# WR.net
KiCad netlist of a schematic drawn in Altium Designer
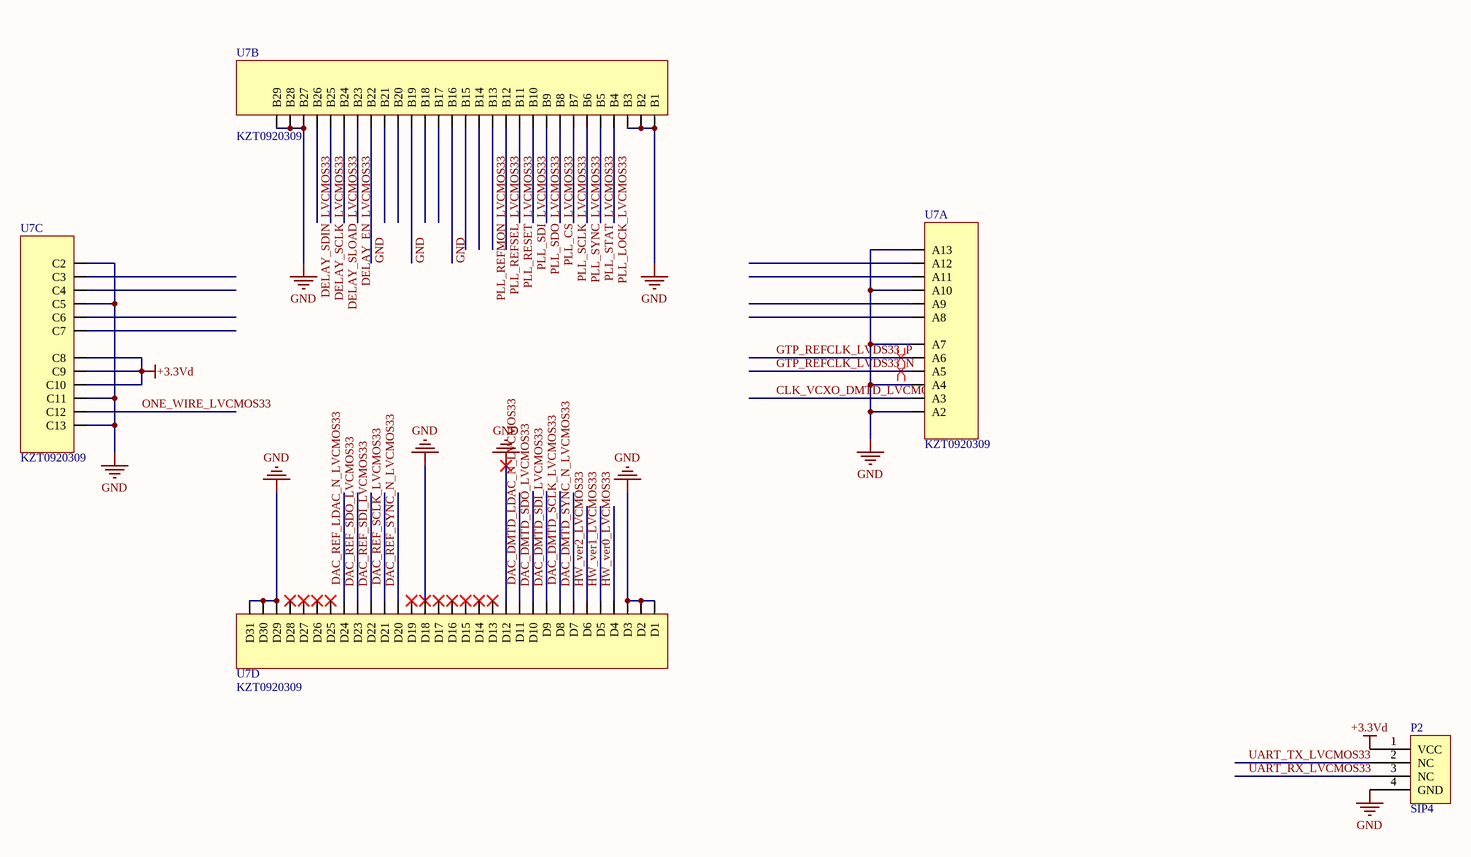
[diagram p0: WR.SchDoc]

(export (version "E")
  (design (tool "Eeschema 10.0.6"))
  (components
    (comp (ref "P2") (value "SIP4") (footprint "HDR1X4") (libsource (lib "LIB01DXP2006SchLib") (part "SIP4")))
    (comp (ref "U7")
      (value "KZT0920309")
      (footprint "KZT0920309")
      (description "NEM&MINI Socket")
      (libsource (lib "LIB01DXP2006SchLib") (part "KZT0920309"))
    )
  )
  (nets
    (net (code "1") (name "+3.3Vd") (class "Default")
      (node (ref "P2") (pin "1") (pinfunction "VCC_1") (pintype "passive"))
      (node (ref "U7") (pin "C10") (pinfunction "C10_C10") (pintype "passive"))
      (node (ref "U7") (pin "C8") (pinfunction "C8_C8") (pintype "passive"))
      (node (ref "U7") (pin "C9") (pinfunction "C9_C9") (pintype "passive"))
    )
    (net (code "2") (name "/CLK_VCXO_DMTD_LVCMOS33") (class "Default")
      (node (ref "U7") (pin "A3") (pinfunction "A3_A3") (pintype "passive"))
    )
    (net (code "3") (name "/DAC_DMTD_LDAC_N_LVCMOS33") (class "Default")
      (node (ref "U7") (pin "D11") (pinfunction "D11_D11") (pintype "power_in"))
    )
    (net (code "4") (name "/DAC_DMTD_SCLK_LVCMOS33") (class "Default")
      (node (ref "U7") (pin "D8") (pinfunction "D8_D8") (pintype "power_in"))
    )
    (net (code "5") (name "/DAC_DMTD_SDI_LVCMOS33") (class "Default")
      (node (ref "U7") (pin "D9") (pinfunction "D9_D9") (pintype "power_in"))
    )
    (net (code "6") (name "/DAC_DMTD_SDO_LVCMOS33") (class "Default")
      (node (ref "U7") (pin "D10") (pinfunction "D10_D10") (pintype "power_in"))
    )
    (net (code "7") (name "/DAC_DMTD_SYNC_N_LVCMOS33") (class "Default")
      (node (ref "U7") (pin "D7") (pinfunction "D7_D7") (pintype "power_in"))
    )
    (net (code "8") (name "/DAC_REF_LDAC_N_LVCMOS33") (class "Default")
      (node (ref "U7") (pin "D24") (pinfunction "D24_D24") (pintype "power_in"))
    )
    (net (code "9") (name "/DAC_REF_SCLK_LVCMOS33") (class "Default")
      (node (ref "U7") (pin "D21") (pinfunction "D21_D21") (pintype "power_in"))
    )
    (net (code "10") (name "/DAC_REF_SDI_LVCMOS33") (class "Default")
      (node (ref "U7") (pin "D22") (pinfunction "D22_D22") (pintype "power_in"))
    )
    (net (code "11") (name "/DAC_REF_SDO_LVCMOS33") (class "Default")
      (node (ref "U7") (pin "D23") (pinfunction "D23_D23") (pintype "power_in"))
    )
    (net (code "12") (name "/DAC_REF_SYNC_N_LVCMOS33") (class "Default")
      (node (ref "U7") (pin "D20") (pinfunction "D20_D20") (pintype "power_in"))
    )
    (net (code "13") (name "/DELAY_EN_LVCMOS33") (class "Default")
      (node (ref "U7") (pin "B23") (pinfunction "B23_B23") (pintype "power_in"))
    )
    (net (code "14") (name "/DELAY_SCLK_LVCMOS33") (class "Default")
      (node (ref "U7") (pin "B25") (pinfunction "B25_B25") (pintype "power_in"))
    )
    (net (code "15") (name "/DELAY_SDIN_LVCMOS33") (class "Default")
      (node (ref "U7") (pin "B26") (pinfunction "B26_B26") (pintype "power_in"))
    )
    (net (code "16") (name "/DELAY_SLOAD_LVCMOS33") (class "Default")
      (node (ref "U7") (pin "B24") (pinfunction "B24_B24") (pintype "power_in"))
    )
    (net (code "17") (name "/GTP_REFCLK_LVDS33_N") (class "Default")
      (node (ref "U7") (pin "A5") (pinfunction "A5_A5") (pintype "passive"))
    )
    (net (code "18") (name "/GTP_REFCLK_LVDS33_P") (class "Default")
      (node (ref "U7") (pin "A6") (pinfunction "A6_A6") (pintype "passive"))
    )
    (net (code "19") (name "/HW_ver0_LVCMOS33") (class "Default")
      (node (ref "U7") (pin "D4") (pinfunction "D4_D4") (pintype "power_in"))
    )
    (net (code "20") (name "/HW_ver1_LVCMOS33") (class "Default")
      (node (ref "U7") (pin "D5") (pinfunction "D5_D5") (pintype "power_in"))
    )
    (net (code "21") (name "/HW_ver2_LVCMOS33") (class "Default")
      (node (ref "U7") (pin "D6") (pinfunction "D6_D6") (pintype "power_in"))
    )
    (net (code "22") (name "/ONE_WIRE_LVCMOS33") (class "Default")
      (node (ref "U7") (pin "C12") (pinfunction "C12_C12") (pintype "passive"))
    )
    (net (code "23") (name "/PLL_CS_LVCMOS33") (class "Default")
      (node (ref "U7") (pin "B8") (pinfunction "B8_B8") (pintype "power_in"))
    )
    (net (code "24") (name "/PLL_LOCK_LVCMOS33") (class "Default")
      (node (ref "U7") (pin "B4") (pinfunction "B4_B4") (pintype "power_in"))
    )
    (net (code "25") (name "/PLL_REFMON_LVCMOS33") (class "Default")
      (node (ref "U7") (pin "B13") (pinfunction "B13_B13") (pintype "power_in"))
    )
    (net (code "26") (name "/PLL_REFSEL_LVCMOS33") (class "Default")
      (node (ref "U7") (pin "B12") (pinfunction "B12_B12") (pintype "power_in"))
    )
    (net (code "27") (name "/PLL_RESET_LVCMOS33") (class "Default")
      (node (ref "U7") (pin "B11") (pinfunction "B11_B11") (pintype "power_in"))
    )
    (net (code "28") (name "/PLL_SCLK_LVCMOS33") (class "Default")
      (node (ref "U7") (pin "B7") (pinfunction "B7_B7") (pintype "power_in"))
    )
    (net (code "29") (name "/PLL_SDI_LVCMOS33") (class "Default")
      (node (ref "U7") (pin "B10") (pinfunction "B10_B10") (pintype "power_in"))
    )
    (net (code "30") (name "/PLL_SDO_LVCMOS33") (class "Default")
      (node (ref "U7") (pin "B9") (pinfunction "B9_B9") (pintype "power_in"))
    )
    (net (code "31") (name "/PLL_STAT_LVCMOS33") (class "Default")
      (node (ref "U7") (pin "B5") (pinfunction "B5_B5") (pintype "power_in"))
    )
    (net (code "32") (name "/PLL_SYNC_LVCMOS33") (class "Default")
      (node (ref "U7") (pin "B6") (pinfunction "B6_B6") (pintype "power_in"))
    )
    (net (code "33") (name "/UART_RX_LVCMOS33") (class "Default")
      (node (ref "P2") (pin "3") (pinfunction "NC_3") (pintype "passive"))
    )
    (net (code "34") (name "/UART_TX_LVCMOS33") (class "Default")
      (node (ref "P2") (pin "2") (pinfunction "NC_2") (pintype "passive"))
    )
    (net (code "35") (name "GND") (class "Default")
      (node (ref "P2") (pin "4") (pinfunction "GND_4") (pintype "passive"))
      (node (ref "U7") (pin "A10") (pinfunction "A10_A10") (pintype "passive"))
      (node (ref "U7") (pin "A13") (pinfunction "A13_A13") (pintype "passive"))
      (node (ref "U7") (pin "A2") (pinfunction "A2_A2") (pintype "passive"))
      (node (ref "U7") (pin "A4") (pinfunction "A4_A4") (pintype "passive"))
      (node (ref "U7") (pin "A7") (pinfunction "A7_A7") (pintype "passive"))
      (node (ref "U7") (pin "B1") (pinfunction "B1_B1") (pintype "power_in"))
      (node (ref "U7") (pin "B16") (pinfunction "B16_B16") (pintype "power_in"))
      (node (ref "U7") (pin "B19") (pinfunction "B19_B19") (pintype "power_in"))
      (node (ref "U7") (pin "B2") (pinfunction "B2_B2") (pintype "power_in"))
      (node (ref "U7") (pin "B22") (pinfunction "B22_B22") (pintype "power_in"))
      (node (ref "U7") (pin "B27") (pinfunction "B27_B27") (pintype "power_in"))
      (node (ref "U7") (pin "B28") (pinfunction "B28_B28") (pintype "power_in"))
      (node (ref "U7") (pin "B29") (pinfunction "B29_B29") (pintype "power_in"))
      (node (ref "U7") (pin "B3") (pinfunction "B3_B3") (pintype "power_in"))
      (node (ref "U7") (pin "C11") (pinfunction "C11_C11") (pintype "passive"))
      (node (ref "U7") (pin "C13") (pinfunction "C13_C13") (pintype "passive"))
      (node (ref "U7") (pin "C2") (pinfunction "C2_C2") (pintype "passive"))
      (node (ref "U7") (pin "C5") (pinfunction "C5_C5") (pintype "passive"))
      (node (ref "U7") (pin "D1") (pinfunction "D1_D1") (pintype "power_in"))
      (node (ref "U7") (pin "D12") (pinfunction "D12_D12") (pintype "power_in"))
      (node (ref "U7") (pin "D18") (pinfunction "D18_D18") (pintype "power_in"))
      (node (ref "U7") (pin "D2") (pinfunction "D2_D2") (pintype "power_in"))
      (node (ref "U7") (pin "D29") (pinfunction "D29_D29") (pintype "power_in"))
      (node (ref "U7") (pin "D3") (pinfunction "D3_D3") (pintype "power_in"))
      (node (ref "U7") (pin "D30") (pinfunction "D30_D30") (pintype "power_in"))
      (node (ref "U7") (pin "D31") (pinfunction "D31_D31") (pintype "power_in"))
    )
    (net (code "36") (name "unconnected-(U7-PadA8)") (class "Default")
      (node (ref "U7") (pin "A8") (pinfunction "A8_A8") (pintype "passive"))
    )
    (net (code "37") (name "unconnected-(U7-PadA9)") (class "Default")
      (node (ref "U7") (pin "A9") (pinfunction "A9_A9") (pintype "passive"))
    )
    (net (code "38") (name "unconnected-(U7-PadA11)") (class "Default")
      (node (ref "U7") (pin "A11") (pinfunction "A11_A11") (pintype "passive"))
    )
    (net (code "39") (name "unconnected-(U7-PadA12)") (class "Default")
      (node (ref "U7") (pin "A12") (pinfunction "A12_A12") (pintype "passive"))
    )
    (net (code "40") (name "unconnected-(U7-PadB14)") (class "Default")
      (node (ref "U7") (pin "B14") (pinfunction "B14_B14") (pintype "power_in"))
    )
    (net (code "41") (name "unconnected-(U7-PadB15)") (class "Default")
      (node (ref "U7") (pin "B15") (pinfunction "B15_B15") (pintype "power_in"))
    )
    (net (code "42") (name "unconnected-(U7-PadB17)") (class "Default")
      (node (ref "U7") (pin "B17") (pinfunction "B17_B17") (pintype "power_in"))
    )
    (net (code "43") (name "unconnected-(U7-PadB18)") (class "Default")
      (node (ref "U7") (pin "B18") (pinfunction "B18_B18") (pintype "power_in"))
    )
    (net (code "44") (name "unconnected-(U7-PadB20)") (class "Default")
      (node (ref "U7") (pin "B20") (pinfunction "B20_B20") (pintype "power_in"))
    )
    (net (code "45") (name "unconnected-(U7-PadB21)") (class "Default")
      (node (ref "U7") (pin "B21") (pinfunction "B21_B21") (pintype "power_in"))
    )
    (net (code "46") (name "unconnected-(U7-PadC3)") (class "Default")
      (node (ref "U7") (pin "C3") (pinfunction "C3_C3") (pintype "passive"))
    )
    (net (code "47") (name "unconnected-(U7-PadC4)") (class "Default")
      (node (ref "U7") (pin "C4") (pinfunction "C4_C4") (pintype "passive"))
    )
    (net (code "48") (name "unconnected-(U7-PadC6)") (class "Default")
      (node (ref "U7") (pin "C6") (pinfunction "C6_C6") (pintype "passive"))
    )
    (net (code "49") (name "unconnected-(U7-PadC7)") (class "Default")
      (node (ref "U7") (pin "C7") (pinfunction "C7_C7") (pintype "passive"))
    )
    (net (code "50") (name "unconnected-(U7-PadD13)") (class "Default")
      (node (ref "U7") (pin "D13") (pinfunction "D13_D13") (pintype "power_in+no_connect"))
    )
    (net (code "51") (name "unconnected-(U7-PadD14)") (class "Default")
      (node (ref "U7") (pin "D14") (pinfunction "D14_D14") (pintype "power_in+no_connect"))
    )
    (net (code "52") (name "unconnected-(U7-PadD15)") (class "Default")
      (node (ref "U7") (pin "D15") (pinfunction "D15_D15") (pintype "power_in+no_connect"))
    )
    (net (code "53") (name "unconnected-(U7-PadD16)") (class "Default")
      (node (ref "U7") (pin "D16") (pinfunction "D16_D16") (pintype "power_in+no_connect"))
    )
    (net (code "54") (name "unconnected-(U7-PadD17)") (class "Default")
      (node (ref "U7") (pin "D17") (pinfunction "D17_D17") (pintype "power_in+no_connect"))
    )
    (net (code "55") (name "unconnected-(U7-PadD19)") (class "Default")
      (node (ref "U7") (pin "D19") (pinfunction "D19_D19") (pintype "power_in+no_connect"))
    )
    (net (code "56") (name "unconnected-(U7-PadD25)") (class "Default")
      (node (ref "U7") (pin "D25") (pinfunction "D25_D25") (pintype "power_in+no_connect"))
    )
    (net (code "57") (name "unconnected-(U7-PadD26)") (class "Default")
      (node (ref "U7") (pin "D26") (pinfunction "D26_D26") (pintype "power_in+no_connect"))
    )
    (net (code "58") (name "unconnected-(U7-PadD27)") (class "Default")
      (node (ref "U7") (pin "D27") (pinfunction "D27_D27") (pintype "power_in+no_connect"))
    )
    (net (code "59") (name "unconnected-(U7-PadD28)") (class "Default")
      (node (ref "U7") (pin "D28") (pinfunction "D28_D28") (pintype "power_in+no_connect"))
    )
  )
)
